# AudioReactiveCircuit_schematic_V1.net
KiCad netlist of a schematic drawn in Altium Designer
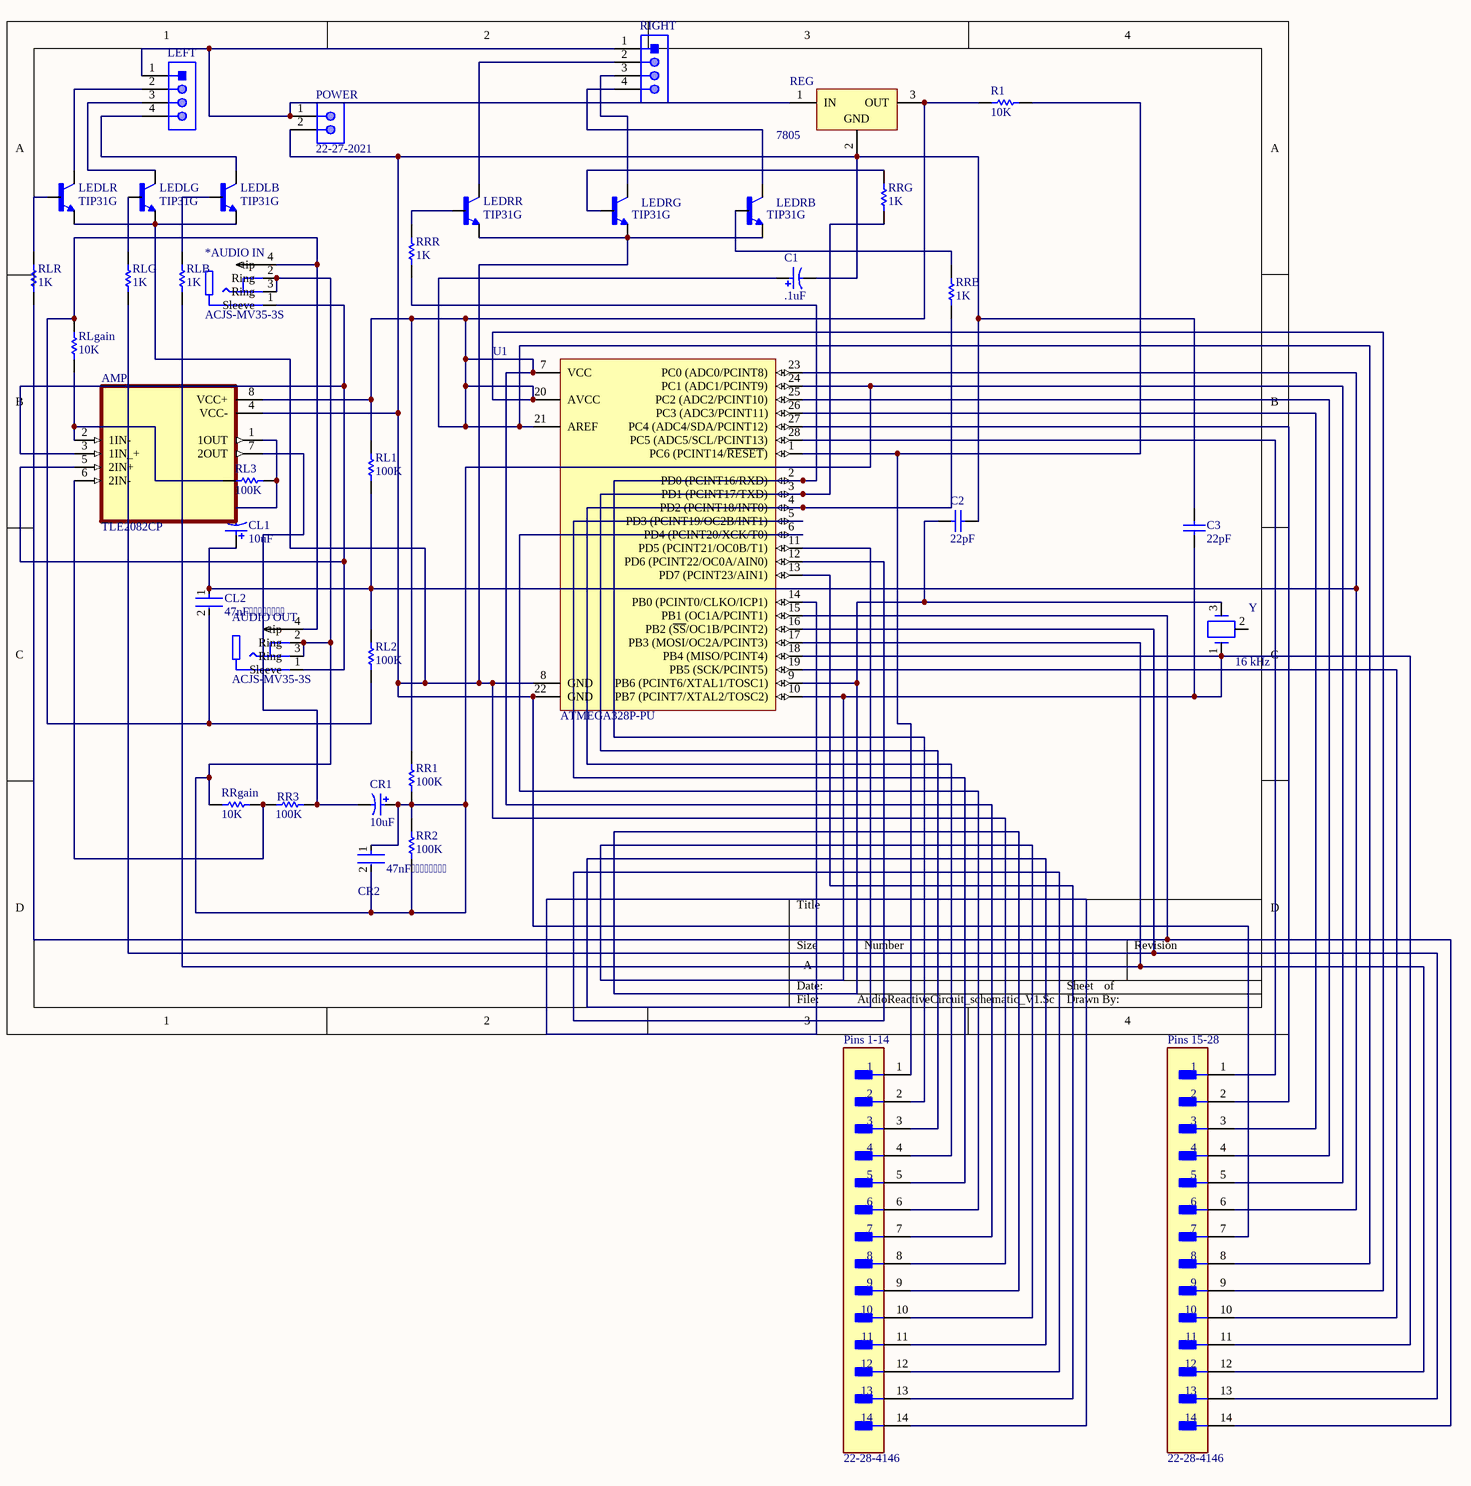
[diagram p0: AudioReactiveCircuit_schematic_V1.SchDoc]

(export (version "E")
  (design (tool "Eeschema 10.0.6"))
  (components
    (comp (ref "*AUDIO IN")
      (value "ACJS-MV35-3S")
      (footprint "AMPHENOL_ACJM-MV35-2S")
      (description "Conn 3.5MM Audio Jack F 3 POS Solder ST Thru-Hole 4 Terminal 1 Port")
      (libsource (lib "University of Pittsburgh") (part "ACJS-MV35-3S-Symbol-1"))
    )
    (comp (ref "AMP")
      (value "TLE2082CP")
      (footprint "DIP794W45P254L959H508Q8")
      (libsource (lib "TLE2082CP") (part "TLE2082CP"))
    )
    (comp (ref "AUDIO OUT")
      (value "ACJS-MV35-3S")
      (footprint "AMPHENOL_ACJM-MV35-2S")
      (description "Conn 3.5MM Audio Jack F 3 POS Solder ST Thru-Hole 4 Terminal 1 Port")
      (libsource (lib "University of Pittsburgh") (part "ACJS-MV35-3S-Symbol-1"))
    )
    (comp (ref "C1")
      (value ".1uF")
      (footprint "CAPPR55-200-1100X500X1200")
      (description "Aluminum Electrolytic Capacitor, 10 uF, +/- 20%, 50 V, -40 to 85 degC, 2-Pin THD, RoHS, Bulk")
      (fields (field (name "MANUFACTURER") "Panasonic") (field (name "TOLERANCE") "20%"))
      (libsource (lib "Altium Content Vault") (part "CAP-P-2"))
    )
    (comp (ref "C2")
      (value "22pF")
      (footprint "KEMT-C315-THT-2")
      (description "Capacitor, Ceramic, 22 pF, +/-10 %, 100 V, -55 to 125 degC, 2-Pin THD, RoHS, Bulk")
      (libsource (lib "Altium Content Vault") (part "CAP-NP-2"))
    )
    (comp (ref "C3")
      (value "22pF")
      (footprint "KEMT-C315-THT-2")
      (description "Capacitor, Ceramic, 22 pF, +/-10 %, 100 V, -55 to 125 degC, 2-Pin THD, RoHS, Bulk")
      (libsource (lib "Altium Content Vault") (part "CAP-NP-2"))
    )
    (comp (ref "CL1")
      (value "10uF")
      (footprint "CAPPR55-200-1100X500X1200")
      (description "Aluminum Electrolytic Capacitor, 10 uF, +/- 20%, 50 V, -40 to 85 degC, 2-Pin THD, RoHS, Bulk")
      (fields (field (name "MANUFACTURER") "Panasonic") (field (name "TOLERANCE") "20%"))
      (libsource (lib "Altium Content Vault") (part "CAP-P-2"))
    )
    (comp (ref "CL2")
      (value "47nF")
      (footprint "FP-RDE2M1-MFG")
      (description "Ceramic Capacitor 47nF ±10% 450V X7T Radial")
      (fields (field (name "TOLERANCE") "10%"))
      (libsource (lib "Altium Content Vault") (part "b4654b650e69147ec39a6b967a45e02"))
    )
    (comp (ref "CR1")
      (value "10uF")
      (footprint "CAPPR55-200-1100X500X1200")
      (description "Aluminum Electrolytic Capacitor, 10 uF, +/- 20%, 50 V, -40 to 85 degC, 2-Pin THD, RoHS, Bulk")
      (fields (field (name "MANUFACTURER") "Panasonic") (field (name "TOLERANCE") "20%"))
      (libsource (lib "Altium Content Vault") (part "CAP-P-2"))
    )
    (comp (ref "CR2")
      (value "47nF")
      (footprint "FP-RDE2M1-MFG")
      (description "Ceramic Capacitor 47nF ±10% 450V X7T Radial")
      (fields (field (name "TOLERANCE") "10%"))
      (libsource (lib "Altium Content Vault") (part "b4654b650e69147ec39a6b967a45e02"))
    )
    (comp (ref "LEDLB")
      (value "TIP31G")
      (footprint "TO254P1060X482X2222-3")
      (description "Bipolar (BJT) Transistor NPN 40 V 3 A 3MHz 2 W Through Hole TO-220")
      (fields (field (name "MF") "ON Semiconductor"))
      (libsource (lib "TIP31G") (part "TIP31G"))
    )
    (comp (ref "LEDLG")
      (value "TIP31G")
      (footprint "TO254P1060X482X2222-3")
      (description "Bipolar (BJT) Transistor NPN 40 V 3 A 3MHz 2 W Through Hole TO-220")
      (fields (field (name "MF") "ON Semiconductor"))
      (libsource (lib "TIP31G") (part "TIP31G"))
    )
    (comp (ref "LEDLR")
      (value "TIP31G")
      (footprint "TO254P1060X482X2222-3")
      (description "Bipolar (BJT) Transistor NPN 40 V 3 A 3MHz 2 W Through Hole TO-220")
      (fields (field (name "MF") "ON Semiconductor"))
      (libsource (lib "TIP31G") (part "TIP31G"))
    )
    (comp (ref "LEDRB")
      (value "TIP31G")
      (footprint "TO254P1060X482X2222-3")
      (description "Bipolar (BJT) Transistor NPN 40 V 3 A 3MHz 2 W Through Hole TO-220")
      (fields (field (name "MF") "ON Semiconductor"))
      (libsource (lib "TIP31G") (part "TIP31G"))
    )
    (comp (ref "LEDRG")
      (value "TIP31G")
      (footprint "TO254P1060X482X2222-3")
      (description "Bipolar (BJT) Transistor NPN 40 V 3 A 3MHz 2 W Through Hole TO-220")
      (fields (field (name "MF") "ON Semiconductor"))
      (libsource (lib "TIP31G") (part "TIP31G"))
    )
    (comp (ref "LEDRR")
      (value "TIP31G")
      (footprint "TO254P1060X482X2222-3")
      (description "Bipolar (BJT) Transistor NPN 40 V 3 A 3MHz 2 W Through Hole TO-220")
      (fields (field (name "MF") "ON Semiconductor"))
      (libsource (lib "TIP31G") (part "TIP31G"))
    )
    (comp (ref "LEFT")
      (value "61300411121")
      (footprint "61300411121")
      (description "THT Vertical Pin Header WR-PHD, Pitch 2.54 mm, Single Row, 4 pins")
      (fields (field (name "MANUFACTURER") "Wurth Elektronik") (field (name "PUBLISHER") "WurthElektronik"))
      (libsource (lib "Altium Content Vault") (part "WE-CN-1P-M-R4"))
    )
    (comp (ref "Pins 1-14")
      (value "22-28-4146")
      (footprint "FP-22-28-4146-MFG")
      (description "CONN HEADER VERT 14POS 2.54MM")
      (libsource (lib "Altium Content Vault") (part "c057707092b1df4b5af47e9e56d9e1e"))
    )
    (comp (ref "Pins 15-28")
      (value "22-28-4146")
      (footprint "FP-22-28-4146-MFG")
      (description "CONN HEADER VERT 14POS 2.54MM")
      (libsource (lib "Altium Content Vault") (part "c057707092b1df4b5af47e9e56d9e1e"))
    )
    (comp (ref "POWER")
      (value "22-27-2021")
      (footprint "MOLX-22-27-2021_V")
      (fields (field (name "MANUFACTURER") "Molex") (field (name "PARTNUMBER") "0022272021"))
      (libsource (lib "Altium Content Vault") (part "CN-1P-M-R2"))
    )
    (comp (ref "R1")
      (value "10K")
      (footprint "RESA60-630X240")
      (description "Axial Resistor, 100 KOhm, +/- 1%, 0.25 W, -55 to 155 degC, 2-Pin THD, RoHS, Bulk")
      (fields (field (name "TOLERANCE") "1%"))
      (libsource (lib "Altium Content Vault") (part "RES-2"))
    )
    (comp (ref "REG")
      (value "7805")
      (footprint "TO220")
      (description "Positive Voltage Regulator, 5V, 3-Pin TO-220")
      (libsource (lib "Altium Content Vault") (part "PM-REG-L4940-SIL3"))
    )
    (comp (ref "RIGHT")
      (value "6")
      (footprint "61300411121")
      (description "THT Vertical Pin Header WR-PHD, Pitch 2.54 mm, Single Row, 4 pins")
      (fields
        (field (name "MANUFACTURER") "Wurth Elektronik")
        (field (name "PART NUMBER") "61300411121")
        (field (name "PUBLISHER") "WurthElektronik")
      )
      (libsource (lib "Altium Content Vault") (part "WE-CN-1P-M-R4"))
    )
    (comp (ref "RL1")
      (value "100K")
      (footprint "RESA60-630X240")
      (description "Axial Resistor, 100 KOhm, +/- 1%, 0.25 W, -55 to 155 degC, 2-Pin THD, RoHS, Bulk")
      (fields (field (name "TOLERANCE") "1%"))
      (libsource (lib "Altium Content Vault") (part "RES-2"))
    )
    (comp (ref "RL2")
      (value "100K")
      (footprint "RESA60-630X240")
      (description "Axial Resistor, 100 KOhm, +/- 1%, 0.25 W, -55 to 155 degC, 2-Pin THD, RoHS, Bulk")
      (fields (field (name "TOLERANCE") "1%"))
      (libsource (lib "Altium Content Vault") (part "RES-2"))
    )
    (comp (ref "RL3")
      (value "100K")
      (footprint "RESA60-630X240")
      (description "Axial Resistor, 100 KOhm, +/- 1%, 0.25 W, -55 to 155 degC, 2-Pin THD, RoHS, Bulk")
      (fields (field (name "TOLERANCE") "1%"))
      (libsource (lib "Altium Content Vault") (part "RES-2"))
    )
    (comp (ref "RLB")
      (value "1K")
      (footprint "RESA60-630X240")
      (description "Axial Resistor, 100 KOhm, +/- 1%, 0.25 W, -55 to 155 degC, 2-Pin THD, RoHS, Bulk")
      (fields (field (name "TOLERANCE") "1%"))
      (libsource (lib "Altium Content Vault") (part "RES-2"))
    )
    (comp (ref "RLG")
      (value "1K")
      (footprint "RESA60-630X240")
      (description "Axial Resistor, 100 KOhm, +/- 1%, 0.25 W, -55 to 155 degC, 2-Pin THD, RoHS, Bulk")
      (fields (field (name "TOLERANCE") "1%"))
      (libsource (lib "Altium Content Vault") (part "RES-2"))
    )
    (comp (ref "RLgain")
      (value "10K")
      (footprint "RESA60-630X240")
      (description "Axial Resistor, 100 KOhm, +/- 1%, 0.25 W, -55 to 155 degC, 2-Pin THD, RoHS, Bulk")
      (fields (field (name "TOLERANCE") "1%"))
      (libsource (lib "Altium Content Vault") (part "RES-2"))
    )
    (comp (ref "RLR")
      (value "1K")
      (footprint "RESA60-630X240")
      (description "Axial Resistor, 100 KOhm, +/- 1%, 0.25 W, -55 to 155 degC, 2-Pin THD, RoHS, Bulk")
      (fields (field (name "TOLERANCE") "1%"))
      (libsource (lib "Altium Content Vault") (part "RES-2"))
    )
    (comp (ref "RR1")
      (value "100K")
      (footprint "RESA60-630X240")
      (description "Axial Resistor, 100 KOhm, +/- 1%, 0.25 W, -55 to 155 degC, 2-Pin THD, RoHS, Bulk")
      (fields (field (name "TOLERANCE") "1%"))
      (libsource (lib "Altium Content Vault") (part "RES-2"))
    )
    (comp (ref "RR2")
      (value "100K")
      (footprint "RESA60-630X240")
      (description "Axial Resistor, 100 KOhm, +/- 1%, 0.25 W, -55 to 155 degC, 2-Pin THD, RoHS, Bulk")
      (fields (field (name "TOLERANCE") "1%"))
      (libsource (lib "Altium Content Vault") (part "RES-2"))
    )
    (comp (ref "RR3")
      (value "100K")
      (footprint "RESA60-630X240")
      (description "Axial Resistor, 100 KOhm, +/- 1%, 0.25 W, -55 to 155 degC, 2-Pin THD, RoHS, Bulk")
      (fields (field (name "TOLERANCE") "1%"))
      (libsource (lib "Altium Content Vault") (part "RES-2"))
    )
    (comp (ref "RRB")
      (value "1K")
      (footprint "RESA60-630X240")
      (description "Axial Resistor, 100 KOhm, +/- 1%, 0.25 W, -55 to 155 degC, 2-Pin THD, RoHS, Bulk")
      (fields (field (name "TOLERANCE") "1%"))
      (libsource (lib "Altium Content Vault") (part "RES-2"))
    )
    (comp (ref "RRG")
      (value "1K")
      (footprint "RESA60-630X240")
      (description "Axial Resistor, 100 KOhm, +/- 1%, 0.25 W, -55 to 155 degC, 2-Pin THD, RoHS, Bulk")
      (fields (field (name "TOLERANCE") "1%"))
      (libsource (lib "Altium Content Vault") (part "RES-2"))
    )
    (comp (ref "RRgain")
      (value "10K")
      (footprint "RESA60-630X240")
      (description "Axial Resistor, 100 KOhm, +/- 1%, 0.25 W, -55 to 155 degC, 2-Pin THD, RoHS, Bulk")
      (fields (field (name "TOLERANCE") "1%"))
      (libsource (lib "Altium Content Vault") (part "RES-2"))
    )
    (comp (ref "RRR")
      (value "1K")
      (footprint "RESA60-630X240")
      (description "Axial Resistor, 100 KOhm, +/- 1%, 0.25 W, -55 to 155 degC, 2-Pin THD, RoHS, Bulk")
      (fields (field (name "TOLERANCE") "1%"))
      (libsource (lib "Altium Content Vault") (part "RES-2"))
    )
    (comp (ref "U1")
      (value "ATMEGA328P-PU")
      (footprint "ATML-28P3")
      (fields (field (name "MANUFACTURER") "Atmel"))
      (libsource (lib "University of Pittsburgh") (part "MC-8B-ATM48-IL28"))
    )
    (comp (ref "Y")
      (value "16 kHz")
      (footprint "ECS-4X-3IL")
      (description "CRYSTAL 8.00 MHZ 20PF 49US")
      (fields (field (name "PARTNUMBER") "ECS-80-20-4X") (field (name "MANUFACTURER") "ECS"))
      (libsource (lib "Altium Content Vault") (part "ECS-ECS-XX-20-4X"))
    )
  )
  (nets
    (net (code "1") (name "Net-(*AUDIO IN-Sleeve)") (class "Default")
      (node (ref "*AUDIO IN") (pin "1") (pinfunction "Sleeve_1") (pintype "passive"))
      (node (ref "AMP") (pin "3") (pinfunction "1IN_+_3") (pintype "input"))
      (node (ref "AMP") (pin "5") (pinfunction "2IN+_5") (pintype "input"))
      (node (ref "AUDIO OUT") (pin "1") (pinfunction "Sleeve_1") (pintype "passive"))
    )
    (net (code "2") (name "Net-(*AUDIO IN-tip)") (class "Default")
      (node (ref "*AUDIO IN") (pin "4") (pinfunction "tip_4") (pintype "passive"))
      (node (ref "AUDIO OUT") (pin "4") (pinfunction "tip_4") (pintype "passive"))
      (node (ref "CL2") (pin "2") (pinfunction "2_2") (pintype "passive"))
      (node (ref "RL2") (pin "1") (pinfunction "1_1") (pintype "passive"))
      (node (ref "RLgain") (pin "2") (pinfunction "2_2") (pintype "passive"))
    )
    (net (code "3") (name "Net-(AMP-1IN-)") (class "Default")
      (node (ref "AMP") (pin "2") (pinfunction "1IN-_2") (pintype "input"))
      (node (ref "RL3") (pin "2") (pinfunction "2_2") (pintype "passive"))
      (node (ref "RLgain") (pin "1") (pinfunction "1_1") (pintype "passive"))
    )
    (net (code "4") (name "Net-(AMP-1OUT)") (class "Default")
      (node (ref "AMP") (pin "1") (pinfunction "1OUT_1") (pintype "output"))
      (node (ref "CL1") (pin "2") (pinfunction "2_2") (pintype "passive"))
      (node (ref "RL3") (pin "1") (pinfunction "1_1") (pintype "passive"))
    )
    (net (code "5") (name "Net-(AMP-2IN-)") (class "Default")
      (node (ref "AMP") (pin "6") (pinfunction "2IN-_6") (pintype "input"))
      (node (ref "RR3") (pin "2") (pinfunction "2_2") (pintype "passive"))
      (node (ref "RRgain") (pin "1") (pinfunction "1_1") (pintype "passive"))
    )
    (net (code "6") (name "Net-(AMP-2OUT)") (class "Default")
      (node (ref "AMP") (pin "7") (pinfunction "2OUT_7") (pintype "output"))
      (node (ref "CR1") (pin "2") (pinfunction "2_2") (pintype "passive"))
      (node (ref "RR3") (pin "1") (pinfunction "1_1") (pintype "passive"))
    )
    (net (code "7") (name "Net-(AMP-VCC+)") (class "Default")
      (node (ref "AMP") (pin "8") (pinfunction "VCC+_8") (pintype "power_in"))
      (node (ref "C1") (pin "1") (pinfunction "1_1") (pintype "passive"))
      (node (ref "Pins 1-14") (pin "7") (pinfunction "7_7") (pintype "passive"))
      (node (ref "Pins 15-28") (pin "8") (pinfunction "8_8") (pintype "passive"))
      (node (ref "Pins 15-28") (pin "9") (pinfunction "9_9") (pintype "passive"))
      (node (ref "R1") (pin "1") (pinfunction "1_1") (pintype "passive"))
      (node (ref "REG") (pin "3") (pinfunction "OUT_3") (pintype "power_in"))
      (node (ref "RL1") (pin "2") (pinfunction "2_2") (pintype "passive"))
      (node (ref "RR1") (pin "2") (pinfunction "2_2") (pintype "passive"))
      (node (ref "U1") (pin "20") (pinfunction "AVCC_20") (pintype "power_in"))
      (node (ref "U1") (pin "21") (pinfunction "AREF_21") (pintype "power_in"))
      (node (ref "U1") (pin "7") (pinfunction "VCC_7") (pintype "power_in"))
    )
    (net (code "8") (name "Net-(AMP-VCC-)") (class "Default")
      (node (ref "AMP") (pin "4") (pinfunction "VCC-_4") (pintype "power_in"))
      (node (ref "C1") (pin "2") (pinfunction "2_2") (pintype "passive"))
      (node (ref "C2") (pin "1") (pinfunction "1_1") (pintype "passive"))
      (node (ref "C3") (pin "2") (pinfunction "2_2") (pintype "passive"))
      (node (ref "LEDLB") (pin "3") (pinfunction "E_3") (pintype "passive"))
      (node (ref "LEDLG") (pin "3") (pinfunction "E_3") (pintype "passive"))
      (node (ref "LEDLR") (pin "3") (pinfunction "E_3") (pintype "passive"))
      (node (ref "LEDRB") (pin "3") (pinfunction "E_3") (pintype "passive"))
      (node (ref "LEDRG") (pin "3") (pinfunction "E_3") (pintype "passive"))
      (node (ref "LEDRR") (pin "3") (pinfunction "E_3") (pintype "passive"))
      (node (ref "POWER") (pin "2") (pinfunction "2_2") (pintype "passive"))
      (node (ref "Pins 1-14") (pin "8") (pinfunction "8_8") (pintype "passive"))
      (node (ref "Pins 15-28") (pin "7") (pinfunction "7_7") (pintype "passive"))
      (node (ref "REG") (pin "2") (pinfunction "GND_2") (pintype "power_in"))
      (node (ref "U1") (pin "22") (pinfunction "GND_22") (pintype "power_in"))
      (node (ref "U1") (pin "8") (pinfunction "GND_8") (pintype "power_in"))
    )
    (net (code "9") (name "Net-(LEDLB-B)") (class "Default")
      (node (ref "LEDLB") (pin "1") (pinfunction "B_1") (pintype "passive"))
      (node (ref "RLB") (pin "2") (pinfunction "2_2") (pintype "passive"))
    )
    (net (code "10") (name "Net-(LEDLB-C)") (class "Default")
      (node (ref "LEDLB") (pin "2") (pinfunction "C_2") (pintype "passive"))
      (node (ref "LEFT") (pin "4") (pinfunction "4_4") (pintype "passive"))
    )
    (net (code "11") (name "Net-(LEDLG-B)") (class "Default")
      (node (ref "LEDLG") (pin "1") (pinfunction "B_1") (pintype "passive"))
      (node (ref "RLG") (pin "1") (pinfunction "1_1") (pintype "passive"))
    )
    (net (code "12") (name "Net-(LEDLG-C)") (class "Default")
      (node (ref "LEDLG") (pin "2") (pinfunction "C_2") (pintype "passive"))
      (node (ref "LEFT") (pin "3") (pinfunction "3_3") (pintype "passive"))
    )
    (net (code "13") (name "Net-(LEDLR-B)") (class "Default")
      (node (ref "LEDLR") (pin "1") (pinfunction "B_1") (pintype "passive"))
      (node (ref "RLR") (pin "1") (pinfunction "1_1") (pintype "passive"))
    )
    (net (code "14") (name "Net-(LEDLR-C)") (class "Default")
      (node (ref "LEDLR") (pin "2") (pinfunction "C_2") (pintype "passive"))
      (node (ref "LEFT") (pin "2") (pinfunction "2_2") (pintype "passive"))
    )
    (net (code "15") (name "Net-(LEDRB-B)") (class "Default")
      (node (ref "LEDRB") (pin "1") (pinfunction "B_1") (pintype "passive"))
      (node (ref "RRB") (pin "2") (pinfunction "2_2") (pintype "passive"))
    )
    (net (code "16") (name "Net-(LEDRB-C)") (class "Default")
      (node (ref "LEDRB") (pin "2") (pinfunction "C_2") (pintype "passive"))
      (node (ref "RIGHT") (pin "4") (pinfunction "4_4") (pintype "passive"))
    )
    (net (code "17") (name "Net-(LEDRG-B)") (class "Default")
      (node (ref "LEDRG") (pin "1") (pinfunction "B_1") (pintype "passive"))
      (node (ref "RRG") (pin "2") (pinfunction "2_2") (pintype "passive"))
    )
    (net (code "18") (name "Net-(LEDRG-C)") (class "Default")
      (node (ref "LEDRG") (pin "2") (pinfunction "C_2") (pintype "passive"))
      (node (ref "RIGHT") (pin "3") (pinfunction "3_3") (pintype "passive"))
    )
    (net (code "19") (name "Net-(LEDRR-B)") (class "Default")
      (node (ref "LEDRR") (pin "1") (pinfunction "B_1") (pintype "passive"))
      (node (ref "RRR") (pin "2") (pinfunction "2_2") (pintype "passive"))
    )
    (net (code "20") (name "Net-(LEDRR-C)") (class "Default")
      (node (ref "LEDRR") (pin "2") (pinfunction "C_2") (pintype "passive"))
      (node (ref "RIGHT") (pin "2") (pinfunction "2_2") (pintype "passive"))
    )
    (net (code "21") (name "Net-(REG-IN)") (class "Default")
      (node (ref "LEFT") (pin "1") (pinfunction "1_1") (pintype "passive"))
      (node (ref "POWER") (pin "1") (pinfunction "1_1") (pintype "passive"))
      (node (ref "REG") (pin "1") (pinfunction "IN_1") (pintype "power_in"))
      (node (ref "RIGHT") (pin "1") (pinfunction "1_1") (pintype "passive"))
    )
    (net (code "22") (name "Net-(U1-PB0_(PCINT0{slash}CLKO{slash}ICP1))") (class "Default")
      (node (ref "Pins 1-14") (pin "14") (pinfunction "14_14") (pintype "passive"))
      (node (ref "U1") (pin "14") (pinfunction "PB0_(PCINT0/CLKO/ICP1)_14") (pintype "bidirectional"))
    )
    (net (code "23") (name "Net-(U1-PB1_(OC1A{slash}PCINT1))") (class "Default")
      (node (ref "Pins 15-28") (pin "14") (pinfunction "14_14") (pintype "passive"))
      (node (ref "RLR") (pin "2") (pinfunction "2_2") (pintype "passive"))
      (node (ref "U1") (pin "15") (pinfunction "PB1_(OC1A/PCINT1)_15") (pintype "bidirectional"))
    )
    (net (code "24") (name "Net-(U1-PB2_(~{SS}{slash}OC1B{slash}PCINT2))") (class "Default")
      (node (ref "Pins 15-28") (pin "13") (pinfunction "13_13") (pintype "passive"))
      (node (ref "RLG") (pin "2") (pinfunction "2_2") (pintype "passive"))
      (node (ref "U1") (pin "16") (pinfunction "PB2_(~{SS}/OC1B/PCINT2)_16") (pintype "bidirectional"))
    )
    (net (code "25") (name "Net-(U1-PB3_(MOSI{slash}OC2A{slash}PCINT3))") (class "Default")
      (node (ref "Pins 15-28") (pin "12") (pinfunction "12_12") (pintype "passive"))
      (node (ref "RLB") (pin "1") (pinfunction "1_1") (pintype "passive"))
      (node (ref "U1") (pin "17") (pinfunction "PB3_(MOSI/OC2A/PCINT3)_17") (pintype "bidirectional"))
    )
    (net (code "26") (name "Net-(U1-PB4_(MISO{slash}PCINT4))") (class "Default")
      (node (ref "C3") (pin "1") (pinfunction "1_1") (pintype "passive"))
      (node (ref "Pins 1-14") (pin "10") (pinfunction "10_10") (pintype "passive"))
      (node (ref "Pins 15-28") (pin "11") (pinfunction "11_11") (pintype "passive"))
      (node (ref "U1") (pin "10") (pinfunction "PB7_(PCINT7/XTAL2/TOSC2)_10") (pintype "bidirectional"))
      (node (ref "U1") (pin "18") (pinfunction "PB4_(MISO/PCINT4)_18") (pintype "bidirectional"))
      (node (ref "Y") (pin "1") (pinfunction "1_1") (pintype "passive"))
    )
    (net (code "27") (name "Net-(U1-PB5_(SCK{slash}PCINT5))") (class "Default")
      (node (ref "Pins 15-28") (pin "10") (pinfunction "10_10") (pintype "passive"))
      (node (ref "U1") (pin "19") (pinfunction "PB5_(SCK/PCINT5)_19") (pintype "bidirectional"))
    )
    (net (code "28") (name "Net-(U1-PB6_(PCINT6{slash}XTAL1{slash}TOSC1))") (class "Default")
      (node (ref "C2") (pin "2") (pinfunction "2_2") (pintype "passive"))
      (node (ref "Pins 1-14") (pin "9") (pinfunction "9_9") (pintype "passive"))
      (node (ref "U1") (pin "9") (pinfunction "PB6_(PCINT6/XTAL1/TOSC1)_9") (pintype "bidirectional"))
      (node (ref "Y") (pin "3") (pinfunction "3_3") (pintype "passive"))
    )
    (net (code "29") (name "Net-(U1-PC0_(ADC0{slash}PCINT8))") (class "Default")
      (node (ref "CL1") (pin "1") (pinfunction "1_1") (pintype "passive"))
      (node (ref "CL2") (pin "1") (pinfunction "1_1") (pintype "passive"))
      (node (ref "Pins 15-28") (pin "6") (pinfunction "6_6") (pintype "passive"))
      (node (ref "RL1") (pin "1") (pinfunction "1_1") (pintype "passive"))
      (node (ref "RL2") (pin "2") (pinfunction "2_2") (pintype "passive"))
      (node (ref "U1") (pin "23") (pinfunction "PC0_(ADC0/PCINT8)_23") (pintype "bidirectional"))
    )
    (net (code "30") (name "Net-(U1-PC1_(ADC1{slash}PCINT9))") (class "Default")
      (node (ref "*AUDIO IN") (pin "2") (pinfunction "Ring_2") (pintype "passive"))
      (node (ref "*AUDIO IN") (pin "3") (pinfunction "Ring_3") (pintype "passive"))
      (node (ref "AUDIO OUT") (pin "2") (pinfunction "Ring_2") (pintype "passive"))
      (node (ref "AUDIO OUT") (pin "3") (pinfunction "Ring_3") (pintype "passive"))
      (node (ref "CR1") (pin "1") (pinfunction "1_1") (pintype "passive"))
      (node (ref "CR2") (pin "1") (pinfunction "1_1") (pintype "passive"))
      (node (ref "CR2") (pin "2") (pinfunction "2_2") (pintype "passive"))
      (node (ref "Pins 15-28") (pin "5") (pinfunction "5_5") (pintype "passive"))
      (node (ref "RR1") (pin "1") (pinfunction "1_1") (pintype "passive"))
      (node (ref "RR2") (pin "1") (pinfunction "1_1") (pintype "passive"))
      (node (ref "RR2") (pin "2") (pinfunction "2_2") (pintype "passive"))
      (node (ref "RRgain") (pin "2") (pinfunction "2_2") (pintype "passive"))
      (node (ref "U1") (pin "24") (pinfunction "PC1_(ADC1/PCINT9)_24") (pintype "bidirectional"))
    )
    (net (code "31") (name "Net-(U1-PC2_(ADC2{slash}PCINT10))") (class "Default")
      (node (ref "Pins 15-28") (pin "4") (pinfunction "4_4") (pintype "passive"))
      (node (ref "U1") (pin "25") (pinfunction "PC2_(ADC2/PCINT10)_25") (pintype "bidirectional"))
    )
    (net (code "32") (name "Net-(U1-PC3_(ADC3{slash}PCINT11))") (class "Default")
      (node (ref "Pins 15-28") (pin "3") (pinfunction "3_3") (pintype "passive"))
      (node (ref "U1") (pin "26") (pinfunction "PC3_(ADC3/PCINT11)_26") (pintype "bidirectional"))
    )
    (net (code "33") (name "Net-(U1-PC4_(ADC4{slash}SDA{slash}PCINT12))") (class "Default")
      (node (ref "Pins 15-28") (pin "2") (pinfunction "2_2") (pintype "passive"))
      (node (ref "U1") (pin "27") (pinfunction "PC4_(ADC4/SDA/PCINT12)_27") (pintype "bidirectional"))
    )
    (net (code "34") (name "Net-(U1-PC5_(ADC5{slash}SCL{slash}PCINT13))") (class "Default")
      (node (ref "Pins 15-28") (pin "1") (pinfunction "1_1") (pintype "passive"))
      (node (ref "U1") (pin "28") (pinfunction "PC5_(ADC5/SCL/PCINT13)_28") (pintype "bidirectional"))
    )
    (net (code "35") (name "Net-(U1-PC6_(PCINT14{slash}~{RESET}))") (class "Default")
      (node (ref "Pins 1-14") (pin "1") (pinfunction "1_1") (pintype "passive"))
      (node (ref "R1") (pin "2") (pinfunction "2_2") (pintype "passive"))
      (node (ref "U1") (pin "1") (pinfunction "PC6_(PCINT14/~{RESET})_1") (pintype "bidirectional"))
    )
    (net (code "36") (name "Net-(U1-PD0_(PCINT16{slash}RXD))") (class "Default")
      (node (ref "Pins 1-14") (pin "2") (pinfunction "2_2") (pintype "passive"))
      (node (ref "RRR") (pin "1") (pinfunction "1_1") (pintype "passive"))
      (node (ref "U1") (pin "2") (pinfunction "PD0_(PCINT16/RXD)_2") (pintype "bidirectional"))
    )
    (net (code "37") (name "Net-(U1-PD1_(PCINT17{slash}TXD))") (class "Default")
      (node (ref "Pins 1-14") (pin "3") (pinfunction "3_3") (pintype "passive"))
      (node (ref "RRG") (pin "1") (pinfunction "1_1") (pintype "passive"))
      (node (ref "U1") (pin "3") (pinfunction "PD1_(PCINT17/TXD)_3") (pintype "bidirectional"))
    )
    (net (code "38") (name "Net-(U1-PD2_(PCINT18{slash}INT0))") (class "Default")
      (node (ref "Pins 1-14") (pin "4") (pinfunction "4_4") (pintype "passive"))
      (node (ref "RRB") (pin "1") (pinfunction "1_1") (pintype "passive"))
      (node (ref "U1") (pin "4") (pinfunction "PD2_(PCINT18/INT0)_4") (pintype "bidirectional"))
    )
    (net (code "39") (name "Net-(U1-PD3_(PCINT19{slash}OC2B{slash}INT1))") (class "Default")
      (node (ref "Pins 1-14") (pin "5") (pinfunction "5_5") (pintype "passive"))
      (node (ref "U1") (pin "5") (pinfunction "PD3_(PCINT19/OC2B/INT1)_5") (pintype "bidirectional"))
    )
    (net (code "40") (name "Net-(U1-PD4_(PCINT20{slash}XCK{slash}T0))") (class "Default")
      (node (ref "Pins 1-14") (pin "6") (pinfunction "6_6") (pintype "passive"))
      (node (ref "U1") (pin "6") (pinfunction "PD4_(PCINT20/XCK/T0)_6") (pintype "bidirectional"))
    )
    (net (code "41") (name "Net-(U1-PD5_(PCINT21{slash}OC0B{slash}T1))") (class "Default")
      (node (ref "Pins 1-14") (pin "11") (pinfunction "11_11") (pintype "passive"))
      (node (ref "U1") (pin "11") (pinfunction "PD5_(PCINT21/OC0B/T1)_11") (pintype "bidirectional"))
    )
    (net (code "42") (name "Net-(U1-PD6_(PCINT22{slash}OC0A{slash}AIN0))") (class "Default")
      (node (ref "Pins 1-14") (pin "12") (pinfunction "12_12") (pintype "passive"))
      (node (ref "U1") (pin "12") (pinfunction "PD6_(PCINT22/OC0A/AIN0)_12") (pintype "bidirectional"))
    )
    (net (code "43") (name "Net-(U1-PD7_(PCINT23{slash}AIN1))") (class "Default")
      (node (ref "Pins 1-14") (pin "13") (pinfunction "13_13") (pintype "passive"))
      (node (ref "U1") (pin "13") (pinfunction "PD7_(PCINT23/AIN1)_13") (pintype "bidirectional"))
    )
    (net (code "44") (name "unconnected-(Y-Pad2)") (class "Default")
      (node (ref "Y") (pin "2") (pinfunction "2_2") (pintype "passive"))
    )
  )
)
